# PCB_DYBoard_Bandmaster_V2_SCH3.net
KiCad netlist of a schematic drawn in Altium Designer
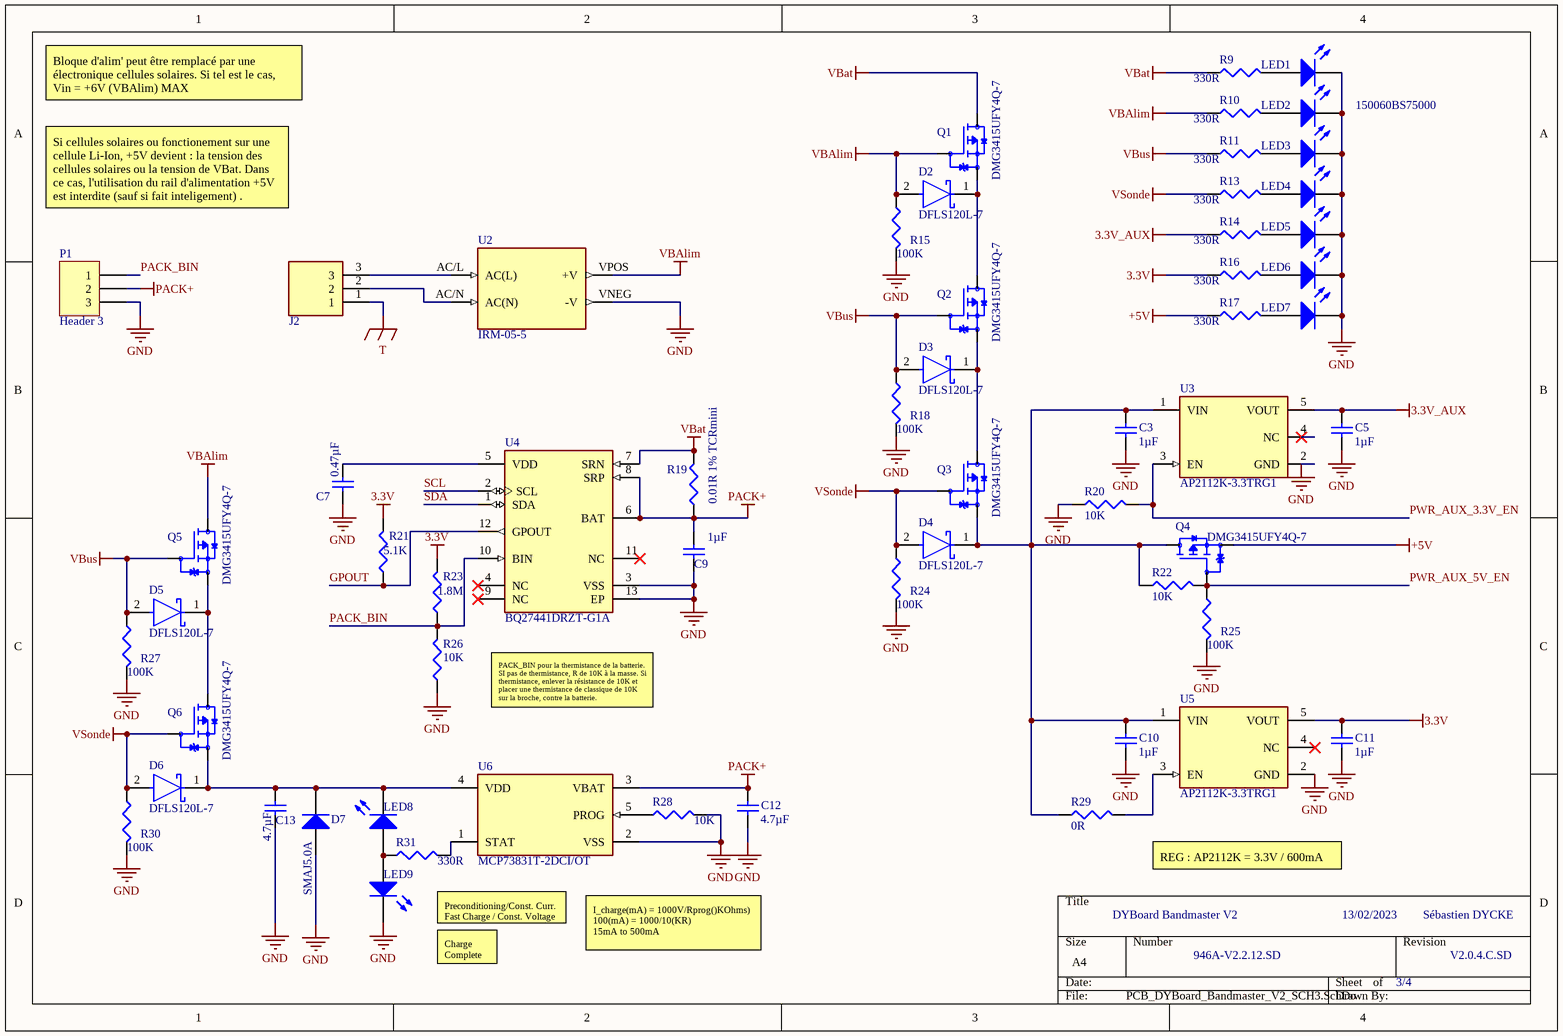
[diagram p0: PCB_DYBoard_Bandmaster_V2_SCH3.SchDoc]

(export (version "E")
  (design (tool "Eeschema 10.0.6"))
  (components
    (comp (ref "C3")
      (value "1µF")
      (footprint "1608[0603]")
      (description "Capacitor (Semiconductor SIM Model)")
      (fields (field (name "Comment") "Cap Semi") (field (name "PUBLISHER") "Altium Limited"))
      (libsource (lib "Miscellaneous Devices") (part "Cap Semi"))
    )
    (comp (ref "C5")
      (value "1µF")
      (footprint "1608[0603]")
      (description "Capacitor (Semiconductor SIM Model)")
      (fields (field (name "Comment") "Cap Semi") (field (name "PUBLISHER") "Altium Limited"))
      (libsource (lib "Miscellaneous Devices") (part "Cap Semi"))
    )
    (comp (ref "C7")
      (value "0.47µF")
      (footprint "1608[0603]")
      (description "Capacitor (Semiconductor SIM Model)")
      (fields (field (name "Comment") "Cap Semi") (field (name "PUBLISHER") "Altium Limited"))
      (libsource (lib "Miscellaneous Devices") (part "Cap Semi"))
    )
    (comp (ref "C9")
      (value "1µF")
      (footprint "1608[0603]")
      (description "Capacitor (Semiconductor SIM Model)")
      (fields (field (name "Comment") "Cap Semi") (field (name "PUBLISHER") "Altium Limited"))
      (libsource (lib "Miscellaneous Devices") (part "Cap Semi"))
    )
    (comp (ref "C10")
      (value "1µF")
      (footprint "1608[0603]")
      (description "Capacitor (Semiconductor SIM Model)")
      (fields (field (name "Comment") "Cap Semi") (field (name "PUBLISHER") "Altium Limited"))
      (libsource (lib "Miscellaneous Devices") (part "Cap Semi"))
    )
    (comp (ref "C11")
      (value "1µF")
      (footprint "1608[0603]")
      (description "Capacitor (Semiconductor SIM Model)")
      (fields (field (name "Comment") "Cap Semi") (field (name "PUBLISHER") "Altium Limited"))
      (libsource (lib "Miscellaneous Devices") (part "Cap Semi"))
    )
    (comp (ref "C12")
      (value "4.7µF")
      (footprint "1608[0603]")
      (description "Capacitor (Semiconductor SIM Model)")
      (fields (field (name "Comment") "Cap Semi") (field (name "PUBLISHER") "Altium Limited"))
      (libsource (lib "Miscellaneous Devices") (part "Cap Semi"))
    )
    (comp (ref "C13")
      (value "4.7µF")
      (footprint "1608[0603]")
      (description "Capacitor (Semiconductor SIM Model)")
      (fields (field (name "Comment") "Cap Semi") (field (name "PUBLISHER") "Altium Limited"))
      (libsource (lib "Miscellaneous Devices") (part "Cap Semi"))
    )
    (comp (ref "D2")
      (value "DFLS120L-7")
      (footprint "FP-PowerDI123-MFG")
      (description "DIODE SCHOTTKY 20V 1A POWERDI123")
      (fields
        (field (name "MANUFACTURER") "Diodes Inc.")
        (field (name "OCTOPART") "https://octopart.com/dfls120l-7-diodes+inc.-328569")
      )
      (libsource (lib "Altium Content Vault") (part "1d6ec82d83fb6aee721767c19dac4b9"))
    )
    (comp (ref "D3")
      (value "DFLS120L-7")
      (footprint "FP-PowerDI123-MFG")
      (description "DIODE SCHOTTKY 20V 1A POWERDI123")
      (fields
        (field (name "MANUFACTURER") "Diodes Inc.")
        (field (name "OCTOPART") "https://octopart.com/dfls120l-7-diodes+inc.-328569")
      )
      (libsource (lib "Altium Content Vault") (part "1d6ec82d83fb6aee721767c19dac4b9"))
    )
    (comp (ref "D4")
      (value "DFLS120L-7")
      (footprint "FP-PowerDI123-MFG")
      (description "DIODE SCHOTTKY 20V 1A POWERDI123")
      (fields
        (field (name "MANUFACTURER") "Diodes Inc.")
        (field (name "OCTOPART") "https://octopart.com/dfls120l-7-diodes+inc.-328569")
      )
      (libsource (lib "Altium Content Vault") (part "1d6ec82d83fb6aee721767c19dac4b9"))
    )
    (comp (ref "D5")
      (value "DFLS120L-7")
      (footprint "FP-PowerDI123-MFG")
      (description "DIODE SCHOTTKY 20V 1A POWERDI123")
      (fields
        (field (name "MANUFACTURER") "Diodes Inc.")
        (field (name "OCTOPART") "https://octopart.com/dfls120l-7-diodes+inc.-328569")
      )
      (libsource (lib "Altium Content Vault") (part "1d6ec82d83fb6aee721767c19dac4b9"))
    )
    (comp (ref "D6")
      (value "DFLS120L-7")
      (footprint "FP-PowerDI123-MFG")
      (description "DIODE SCHOTTKY 20V 1A POWERDI123")
      (fields
        (field (name "MANUFACTURER") "Diodes Inc.")
        (field (name "OCTOPART") "https://octopart.com/dfls120l-7-diodes+inc.-328569")
      )
      (libsource (lib "Altium Content Vault") (part "1d6ec82d83fb6aee721767c19dac4b9"))
    )
    (comp (ref "D7")
      (value "SMAJ5.0A")
      (footprint "BOUR-SMA-2_V")
      (fields (field (name "MANUFACTURER") "Bourns"))
      (libsource (lib "Altium Content Vault") (part "D-AK-2"))
    )
    (comp (ref "J2")
      (value "TBP02R2-381-03BE")
      (footprint "CUI_TBP02R2-381-03BE")
      (description "2~24 Poles, Pluggable, Receptacle, Vertical, 3.81 Pitch, Terminal Block Connector")
      (fields (field (name "MF") "CUI Devices"))
      (libsource (lib "TBP02R2-381-03BE") (part "TBP02R2-381-03BE"))
    )
    (comp (ref "LED1")
      (value "150060BS75000")
      (footprint "0603_A")
      (description "SMD mono-color Chip LED, WL-SMCW, Blue")
      (fields (field (name "MANUFACTURER") "Wuerth Elektronik"))
      (libsource (lib "Altium Content Vault") (part "WE-LED_K1A2-2"))
    )
    (comp (ref "LED2")
      (value "150060BS75000")
      (footprint "0603_A")
      (description "SMD mono-color Chip LED, WL-SMCW, Blue")
      (fields (field (name "MANUFACTURER") "Wuerth Elektronik"))
      (libsource (lib "Altium Content Vault") (part "WE-LED_K1A2-2"))
    )
    (comp (ref "LED3")
      (value "150060BS75000")
      (footprint "0603_A")
      (description "SMD mono-color Chip LED, WL-SMCW, Blue")
      (fields (field (name "MANUFACTURER") "Wuerth Elektronik"))
      (libsource (lib "Altium Content Vault") (part "WE-LED_K1A2-2"))
    )
    (comp (ref "LED4")
      (value "150060BS75000")
      (footprint "0603_A")
      (description "SMD mono-color Chip LED, WL-SMCW, Blue")
      (fields (field (name "MANUFACTURER") "Wuerth Elektronik"))
      (libsource (lib "Altium Content Vault") (part "WE-LED_K1A2-2"))
    )
    (comp (ref "LED5")
      (value "150060BS75000")
      (footprint "0603_A")
      (description "SMD mono-color Chip LED, WL-SMCW, Blue")
      (fields (field (name "MANUFACTURER") "Wuerth Elektronik"))
      (libsource (lib "Altium Content Vault") (part "WE-LED_K1A2-2"))
    )
    (comp (ref "LED6")
      (value "150060BS75000")
      (footprint "0603_A")
      (description "SMD mono-color Chip LED, WL-SMCW, Blue")
      (fields (field (name "MANUFACTURER") "Wuerth Elektronik"))
      (libsource (lib "Altium Content Vault") (part "WE-LED_K1A2-2"))
    )
    (comp (ref "LED7")
      (value "150060BS75000")
      (footprint "0603_A")
      (description "SMD mono-color Chip LED, WL-SMCW, Blue")
      (fields (field (name "MANUFACTURER") "Wuerth Elektronik"))
      (libsource (lib "Altium Content Vault") (part "WE-LED_K1A2-2"))
    )
    (comp (ref "LED8")
      (value "150060BS75000")
      (footprint "0603_A")
      (description "SMD mono-color Chip LED, WL-SMCW, Blue")
      (fields (field (name "MANUFACTURER") "Wuerth Elektronik"))
      (libsource (lib "Altium Content Vault") (part "WE-LED_K1A2-2"))
    )
    (comp (ref "LED9")
      (value "150060BS75000")
      (footprint "0603_A")
      (description "SMD mono-color Chip LED, WL-SMCW, Blue")
      (fields (field (name "MANUFACTURER") "Wuerth Elektronik"))
      (libsource (lib "Altium Content Vault") (part "WE-LED_K1A2-2"))
    )
    (comp (ref "P1")
      (value "Header 3")
      (footprint "HDR1X3")
      (description "Header, 3-Pin")
      (fields (field (name "PUBLISHER") "Altium Limited"))
      (libsource (lib "Miscellaneous Connectors") (part "Header 3"))
    )
    (comp (ref "Q1")
      (value "DMG3415UFY4Q-7")
      (footprint "TRANS_DMG3415UFY4Q-7")
      (description "P-Channel 16V 2.5A _Ta_ 650mW _Ta_ Surface Mount X2-DFN2015-3")
      (fields (field (name "MF") "Diodes Inc.") (field (name "DIGI-KEY_PART_NUMBER") "DMG3415UFY4Q-7DICT-ND"))
      (libsource (lib "DMG3415UFY4Q-7") (part "DMG3415UFY4Q-7"))
    )
    (comp (ref "Q2")
      (value "DMG3415UFY4Q-7")
      (footprint "TRANS_DMG3415UFY4Q-7")
      (description "P-Channel 16V 2.5A _Ta_ 650mW _Ta_ Surface Mount X2-DFN2015-3")
      (fields (field (name "MF") "Diodes Inc.") (field (name "DIGI-KEY_PART_NUMBER") "DMG3415UFY4Q-7DICT-ND"))
      (libsource (lib "DMG3415UFY4Q-7") (part "DMG3415UFY4Q-7"))
    )
    (comp (ref "Q3")
      (value "DMG3415UFY4Q-7")
      (footprint "TRANS_DMG3415UFY4Q-7")
      (description "P-Channel 16V 2.5A _Ta_ 650mW _Ta_ Surface Mount X2-DFN2015-3")
      (fields (field (name "MF") "Diodes Inc.") (field (name "DIGI-KEY_PART_NUMBER") "DMG3415UFY4Q-7DICT-ND"))
      (libsource (lib "DMG3415UFY4Q-7") (part "DMG3415UFY4Q-7"))
    )
    (comp (ref "Q4")
      (value "DMG3415UFY4Q-7")
      (footprint "TRANS_DMG3415UFY4Q-7")
      (description "P-Channel 16V 2.5A _Ta_ 650mW _Ta_ Surface Mount X2-DFN2015-3")
      (fields (field (name "MF") "Diodes Inc.") (field (name "DIGI-KEY_PART_NUMBER") "DMG3415UFY4Q-7DICT-ND"))
      (libsource (lib "DMG3415UFY4Q-7") (part "DMG3415UFY4Q-7"))
    )
    (comp (ref "Q5")
      (value "DMG3415UFY4Q-7")
      (footprint "TRANS_DMG3415UFY4Q-7")
      (description "P-Channel 16V 2.5A _Ta_ 650mW _Ta_ Surface Mount X2-DFN2015-3")
      (fields (field (name "MF") "Diodes Inc.") (field (name "DIGI-KEY_PART_NUMBER") "DMG3415UFY4Q-7DICT-ND"))
      (libsource (lib "DMG3415UFY4Q-7") (part "DMG3415UFY4Q-7"))
    )
    (comp (ref "Q6")
      (value "DMG3415UFY4Q-7")
      (footprint "TRANS_DMG3415UFY4Q-7")
      (description "P-Channel 16V 2.5A _Ta_ 650mW _Ta_ Surface Mount X2-DFN2015-3")
      (fields (field (name "MF") "Diodes Inc.") (field (name "DIGI-KEY_PART_NUMBER") "DMG3415UFY4Q-7DICT-ND"))
      (libsource (lib "DMG3415UFY4Q-7") (part "DMG3415UFY4Q-7"))
    )
    (comp (ref "R9")
      (value "330R")
      (footprint "J1-0603")
      (description "Resistor")
      (fields (field (name "Comment") "Res3") (field (name "PUBLISHER") "Altium Limited"))
      (libsource (lib "Miscellaneous Devices") (part "Res3"))
    )
    (comp (ref "R10")
      (value "330R")
      (footprint "J1-0603")
      (description "Resistor")
      (fields (field (name "Comment") "Res3") (field (name "PUBLISHER") "Altium Limited"))
      (libsource (lib "Miscellaneous Devices") (part "Res3"))
    )
    (comp (ref "R11")
      (value "330R")
      (footprint "J1-0603")
      (description "Resistor")
      (fields (field (name "Comment") "Res3") (field (name "PUBLISHER") "Altium Limited"))
      (libsource (lib "Miscellaneous Devices") (part "Res3"))
    )
    (comp (ref "R13")
      (value "330R")
      (footprint "J1-0603")
      (description "Resistor")
      (fields (field (name "Comment") "Res3") (field (name "PUBLISHER") "Altium Limited"))
      (libsource (lib "Miscellaneous Devices") (part "Res3"))
    )
    (comp (ref "R14")
      (value "330R")
      (footprint "J1-0603")
      (description "Resistor")
      (fields (field (name "Comment") "Res3") (field (name "PUBLISHER") "Altium Limited"))
      (libsource (lib "Miscellaneous Devices") (part "Res3"))
    )
    (comp (ref "R15")
      (value "100K")
      (footprint "J1-0603")
      (description "Resistor")
      (fields (field (name "Comment") "Res3") (field (name "PUBLISHER") "Altium Limited"))
      (libsource (lib "Miscellaneous Devices") (part "Res3"))
    )
    (comp (ref "R16")
      (value "330R")
      (footprint "J1-0603")
      (description "Resistor")
      (fields (field (name "Comment") "Res3") (field (name "PUBLISHER") "Altium Limited"))
      (libsource (lib "Miscellaneous Devices") (part "Res3"))
    )
    (comp (ref "R17")
      (value "330R")
      (footprint "J1-0603")
      (description "Resistor")
      (fields (field (name "Comment") "Res3") (field (name "PUBLISHER") "Altium Limited"))
      (libsource (lib "Miscellaneous Devices") (part "Res3"))
    )
    (comp (ref "R18")
      (value "100K")
      (footprint "J1-0603")
      (description "Resistor")
      (fields (field (name "Comment") "Res3") (field (name "PUBLISHER") "Altium Limited"))
      (libsource (lib "Miscellaneous Devices") (part "Res3"))
    )
    (comp (ref "R19")
      (value "0.01R 1% TCRmini")
      (footprint "J1-0603")
      (description "Resistor")
      (fields (field (name "Comment") "Res3") (field (name "PUBLISHER") "Altium Limited"))
      (libsource (lib "Miscellaneous Devices") (part "Res3"))
    )
    (comp (ref "R20")
      (value "10K")
      (footprint "J1-0603")
      (description "Resistor")
      (fields (field (name "Comment") "Res3") (field (name "PUBLISHER") "Altium Limited"))
      (libsource (lib "Miscellaneous Devices") (part "Res3"))
    )
    (comp (ref "R21")
      (value "5.1K")
      (footprint "J1-0603")
      (description "Resistor")
      (fields (field (name "Comment") "Res3") (field (name "PUBLISHER") "Altium Limited"))
      (libsource (lib "Miscellaneous Devices") (part "Res3"))
    )
    (comp (ref "R22")
      (value "10K")
      (footprint "J1-0603")
      (description "Resistor")
      (fields (field (name "Comment") "Res3") (field (name "PUBLISHER") "Altium Limited"))
      (libsource (lib "Miscellaneous Devices") (part "Res3"))
    )
    (comp (ref "R23")
      (value "1.8M")
      (footprint "J1-0603")
      (description "Resistor")
      (fields (field (name "Comment") "Res3") (field (name "PUBLISHER") "Altium Limited"))
      (libsource (lib "Miscellaneous Devices") (part "Res3"))
    )
    (comp (ref "R24")
      (value "100K")
      (footprint "J1-0603")
      (description "Resistor")
      (fields (field (name "Comment") "Res3") (field (name "PUBLISHER") "Altium Limited"))
      (libsource (lib "Miscellaneous Devices") (part "Res3"))
    )
    (comp (ref "R25")
      (value "100K")
      (footprint "J1-0603")
      (description "Resistor")
      (fields (field (name "Comment") "Res3") (field (name "PUBLISHER") "Altium Limited"))
      (libsource (lib "Miscellaneous Devices") (part "Res3"))
    )
    (comp (ref "R26")
      (value "10K")
      (footprint "J1-0603")
      (description "Resistor")
      (fields (field (name "Comment") "Res3") (field (name "PUBLISHER") "Altium Limited"))
      (libsource (lib "Miscellaneous Devices") (part "Res3"))
    )
    (comp (ref "R27")
      (value "100K")
      (footprint "J1-0603")
      (description "Resistor")
      (fields (field (name "Comment") "Res3") (field (name "PUBLISHER") "Altium Limited"))
      (libsource (lib "Miscellaneous Devices") (part "Res3"))
    )
    (comp (ref "R28")
      (value "10K")
      (footprint "J1-0603")
      (description "Resistor")
      (fields (field (name "Comment") "Res3") (field (name "PUBLISHER") "Altium Limited"))
      (libsource (lib "Miscellaneous Devices") (part "Res3"))
    )
    (comp (ref "R29")
      (value "0R")
      (footprint "J1-0603")
      (description "Resistor")
      (fields (field (name "Comment") "Res3") (field (name "PUBLISHER") "Altium Limited"))
      (libsource (lib "Miscellaneous Devices") (part "Res3"))
    )
    (comp (ref "R30")
      (value "100K")
      (footprint "J1-0603")
      (description "Resistor")
      (fields (field (name "Comment") "Res3") (field (name "PUBLISHER") "Altium Limited"))
      (libsource (lib "Miscellaneous Devices") (part "Res3"))
    )
    (comp (ref "R31")
      (value "330R")
      (footprint "J1-0603")
      (description "Resistor")
      (fields (field (name "Comment") "Res3") (field (name "PUBLISHER") "Altium Limited"))
      (libsource (lib "Miscellaneous Devices") (part "Res3"))
    )
    (comp (ref "U2")
      (value "IRM-05-5")
      (footprint "CONV_IRM-05-5")
      (description "Enclosed AC DC Converters 1 Uitgang 5V 1A 85 ~ 305 VAC, 120 ~ 430 VDC Input")
      (fields (field (name "MF") "MEAN WELL"))
      (libsource (lib "IRM-05-5") (part "IRM-05-5"))
    )
    (comp (ref "U3")
      (value "AP2112K-3.3TRG1")
      (footprint "FP-SOT25-IPC_A")
      (description "IC REG LINEAR 3.3V 600MA SOT25")
      (libsource (lib "Altium Content Vault") (part "c8ab751aee5229183125ab046a11caa"))
    )
    (comp (ref "U4")
      (value "BQ27441DRZT-G1A")
      (footprint "FP-DRZ0012A-MFG")
      (description "IC BATT FUEL GAUGE LICOO2 12SON")
      (fields
        (field (name "OCTOPART") "https://octopart.com/bq27441drzt-g1a-texas+instruments-30555831")
        (field (name "MANUFACTURER") "Texas Instruments")
      )
      (libsource (lib "Altium Content Vault") (part "c803e035ce0891ae19034f27297cdee"))
    )
    (comp (ref "U5")
      (value "AP2112K-3.3TRG1")
      (footprint "FP-SOT25-IPC_A")
      (description "IC REG LINEAR 3.3V 600MA SOT25")
      (libsource (lib "Altium Content Vault") (part "c8ab751aee5229183125ab046a11caa"))
    )
    (comp (ref "U6")
      (value "MCP73831T-2DCI/OT")
      (footprint "FP-C04-091-OT-IPC_B")
      (description "IC CONTROLLR LI-ION 4.2V SOT23-5")
      (libsource (lib "Altium Content Vault") (part "61f5a3bb3429d9e0caadea342aa3b19"))
    )
  )
  (nets
    (net (code "1") (name "+5V") (class "Default")
      (node (ref "Q4") (pin "2") (pinfunction "S_2") (pintype "passive"))
      (node (ref "R17") (pin "1") (pinfunction "1_1") (pintype "passive"))
    )
    (net (code "2") (name "/GPOUT") (class "Default")
      (node (ref "R21") (pin "1") (pinfunction "1_1") (pintype "passive"))
      (node (ref "U4") (pin "12") (pinfunction "GPOUT_12") (pintype "output"))
    )
    (net (code "3") (name "/PACK_BIN") (class "Default")
      (node (ref "P1") (pin "1") (pinfunction "1_1") (pintype "passive"))
      (node (ref "R23") (pin "1") (pinfunction "1_1") (pintype "passive"))
      (node (ref "R26") (pin "2") (pinfunction "2_2") (pintype "passive"))
      (node (ref "U4") (pin "10") (pinfunction "BIN_10") (pintype "input"))
    )
    (net (code "4") (name "/PWR_AUX_3.3V_EN") (class "Default")
      (node (ref "R20") (pin "2") (pinfunction "2_2") (pintype "passive"))
      (node (ref "U3") (pin "3") (pinfunction "EN_3") (pintype "input"))
    )
    (net (code "5") (name "/PWR_AUX_5V_EN") (class "Default")
      (node (ref "Q4") (pin "1") (pinfunction "G_1") (pintype "passive"))
      (node (ref "R22") (pin "2") (pinfunction "2_2") (pintype "passive"))
      (node (ref "R25") (pin "1") (pinfunction "1_1") (pintype "passive"))
    )
    (net (code "6") (name "/SCL") (class "Default")
      (node (ref "U4") (pin "2") (pinfunction "SCL_2") (pintype "bidirectional"))
    )
    (net (code "7") (name "/SDA") (class "Default")
      (node (ref "U4") (pin "1") (pinfunction "SDA_1") (pintype "bidirectional"))
    )
    (net (code "8") (name "3.3V") (class "Default")
      (node (ref "C11") (pin "2") (pinfunction "2_2") (pintype "passive"))
      (node (ref "R16") (pin "1") (pinfunction "1_1") (pintype "passive"))
      (node (ref "R21") (pin "2") (pinfunction "2_2") (pintype "passive"))
      (node (ref "R23") (pin "2") (pinfunction "2_2") (pintype "passive"))
      (node (ref "U5") (pin "5") (pinfunction "VOUT_5") (pintype "power_in"))
    )
    (net (code "9") (name "3.3V_AUX") (class "Default")
      (node (ref "C5") (pin "2") (pinfunction "2_2") (pintype "passive"))
      (node (ref "R14") (pin "1") (pinfunction "1_1") (pintype "passive"))
      (node (ref "U3") (pin "5") (pinfunction "VOUT_5") (pintype "power_in"))
    )
    (net (code "10") (name "GND") (class "Default")
      (node (ref "C10") (pin "1") (pinfunction "1_1") (pintype "passive"))
      (node (ref "C11") (pin "1") (pinfunction "1_1") (pintype "passive"))
      (node (ref "C12") (pin "1") (pinfunction "1_1") (pintype "passive"))
      (node (ref "C13") (pin "1") (pinfunction "1_1") (pintype "passive"))
      (node (ref "C3") (pin "1") (pinfunction "1_1") (pintype "passive"))
      (node (ref "C5") (pin "1") (pinfunction "1_1") (pintype "passive"))
      (node (ref "C7") (pin "1") (pinfunction "1_1") (pintype "passive"))
      (node (ref "C9") (pin "1") (pinfunction "1_1") (pintype "passive"))
      (node (ref "D7") (pin "1") (pinfunction "A_1") (pintype "passive"))
      (node (ref "LED1") (pin "1") (pinfunction "K_1") (pintype "passive"))
      (node (ref "LED2") (pin "1") (pinfunction "K_1") (pintype "passive"))
      (node (ref "LED3") (pin "1") (pinfunction "K_1") (pintype "passive"))
      (node (ref "LED4") (pin "1") (pinfunction "K_1") (pintype "passive"))
      (node (ref "LED5") (pin "1") (pinfunction "K_1") (pintype "passive"))
      (node (ref "LED6") (pin "1") (pinfunction "K_1") (pintype "passive"))
      (node (ref "LED7") (pin "1") (pinfunction "K_1") (pintype "passive"))
      (node (ref "LED9") (pin "1") (pinfunction "K_1") (pintype "passive"))
      (node (ref "P1") (pin "3") (pinfunction "3_3") (pintype "passive"))
      (node (ref "R15") (pin "2") (pinfunction "2_2") (pintype "passive"))
      (node (ref "R18") (pin "2") (pinfunction "2_2") (pintype "passive"))
      (node (ref "R20") (pin "1") (pinfunction "1_1") (pintype "passive"))
      (node (ref "R24") (pin "2") (pinfunction "2_2") (pintype "passive"))
      (node (ref "R25") (pin "2") (pinfunction "2_2") (pintype "passive"))
      (node (ref "R26") (pin "1") (pinfunction "1_1") (pintype "passive"))
      (node (ref "R27") (pin "2") (pinfunction "2_2") (pintype "passive"))
      (node (ref "R28") (pin "2") (pinfunction "2_2") (pintype "passive"))
      (node (ref "R30") (pin "2") (pinfunction "2_2") (pintype "passive"))
      (node (ref "U2") (pin "VNEG") (pinfunction "-V_VNEG") (pintype "output"))
      (node (ref "U3") (pin "2") (pinfunction "GND_2") (pintype "power_in"))
      (node (ref "U4") (pin "13") (pinfunction "EP_13") (pintype "power_in"))
      (node (ref "U4") (pin "3") (pinfunction "VSS_3") (pintype "power_in"))
      (node (ref "U5") (pin "2") (pinfunction "GND_2") (pintype "power_in"))
      (node (ref "U6") (pin "2") (pinfunction "VSS_2") (pintype "power_in"))
    )
    (net (code "11") (name "Net-(D2-C)") (class "Default")
      (node (ref "D2") (pin "1") (pinfunction "C_1") (pintype "passive"))
      (node (ref "Q1") (pin "2") (pinfunction "S_2") (pintype "passive"))
      (node (ref "Q2") (pin "3") (pinfunction "D_3") (pintype "passive"))
    )
    (net (code "12") (name "Net-(D3-C)") (class "Default")
      (node (ref "D3") (pin "1") (pinfunction "C_1") (pintype "passive"))
      (node (ref "Q2") (pin "2") (pinfunction "S_2") (pintype "passive"))
      (node (ref "Q3") (pin "3") (pinfunction "D_3") (pintype "passive"))
    )
    (net (code "13") (name "Net-(D4-C)") (class "Default")
      (node (ref "C10") (pin "2") (pinfunction "2_2") (pintype "passive"))
      (node (ref "C3") (pin "2") (pinfunction "2_2") (pintype "passive"))
      (node (ref "D4") (pin "1") (pinfunction "C_1") (pintype "passive"))
      (node (ref "Q3") (pin "2") (pinfunction "S_2") (pintype "passive"))
      (node (ref "Q4") (pin "3") (pinfunction "D_3") (pintype "passive"))
      (node (ref "R22") (pin "1") (pinfunction "1_1") (pintype "passive"))
      (node (ref "R29") (pin "1") (pinfunction "1_1") (pintype "passive"))
      (node (ref "U3") (pin "1") (pinfunction "VIN_1") (pintype "power_in"))
      (node (ref "U5") (pin "1") (pinfunction "VIN_1") (pintype "power_in"))
    )
    (net (code "14") (name "Net-(D5-C)") (class "Default")
      (node (ref "D5") (pin "1") (pinfunction "C_1") (pintype "passive"))
      (node (ref "Q5") (pin "2") (pinfunction "S_2") (pintype "passive"))
      (node (ref "Q6") (pin "3") (pinfunction "D_3") (pintype "passive"))
    )
    (net (code "15") (name "Net-(D6-C)") (class "Default")
      (node (ref "C13") (pin "2") (pinfunction "2_2") (pintype "passive"))
      (node (ref "D6") (pin "1") (pinfunction "C_1") (pintype "passive"))
      (node (ref "D7") (pin "2") (pinfunction "K_2") (pintype "passive"))
      (node (ref "LED8") (pin "1") (pinfunction "K_1") (pintype "passive"))
      (node (ref "Q6") (pin "2") (pinfunction "S_2") (pintype "passive"))
      (node (ref "U6") (pin "4") (pinfunction "VDD_4") (pintype "open_emitter"))
    )
    (net (code "16") (name "Net-(LED1-A)") (class "Default")
      (node (ref "LED1") (pin "2") (pinfunction "A_2") (pintype "passive"))
      (node (ref "R9") (pin "2") (pinfunction "2_2") (pintype "passive"))
    )
    (net (code "17") (name "Net-(LED2-A)") (class "Default")
      (node (ref "LED2") (pin "2") (pinfunction "A_2") (pintype "passive"))
      (node (ref "R10") (pin "2") (pinfunction "2_2") (pintype "passive"))
    )
    (net (code "18") (name "Net-(LED3-A)") (class "Default")
      (node (ref "LED3") (pin "2") (pinfunction "A_2") (pintype "passive"))
      (node (ref "R11") (pin "2") (pinfunction "2_2") (pintype "passive"))
    )
    (net (code "19") (name "Net-(LED4-A)") (class "Default")
      (node (ref "LED4") (pin "2") (pinfunction "A_2") (pintype "passive"))
      (node (ref "R13") (pin "2") (pinfunction "2_2") (pintype "passive"))
    )
    (net (code "20") (name "Net-(LED5-A)") (class "Default")
      (node (ref "LED5") (pin "2") (pinfunction "A_2") (pintype "passive"))
      (node (ref "R14") (pin "2") (pinfunction "2_2") (pintype "passive"))
    )
    (net (code "21") (name "Net-(LED6-A)") (class "Default")
      (node (ref "LED6") (pin "2") (pinfunction "A_2") (pintype "passive"))
      (node (ref "R16") (pin "2") (pinfunction "2_2") (pintype "passive"))
    )
    (net (code "22") (name "Net-(LED7-A)") (class "Default")
      (node (ref "LED7") (pin "2") (pinfunction "A_2") (pintype "passive"))
      (node (ref "R17") (pin "2") (pinfunction "2_2") (pintype "passive"))
    )
    (net (code "23") (name "Net-(LED8-A)") (class "Default")
      (node (ref "LED8") (pin "2") (pinfunction "A_2") (pintype "passive"))
      (node (ref "LED9") (pin "2") (pinfunction "A_2") (pintype "passive"))
      (node (ref "R31") (pin "1") (pinfunction "1_1") (pintype "passive"))
    )
    (net (code "24") (name "Net-(U2-AC(L))") (class "Default")
      (node (ref "J2") (pin "3") (pinfunction "3_3") (pintype "passive"))
      (node (ref "U2") (pin "AC/L") (pinfunction "AC(L)_AC/L") (pintype "input"))
    )
    (net (code "25") (name "Net-(U2-AC(N))") (class "Default")
      (node (ref "J2") (pin "2") (pinfunction "2_2") (pintype "passive"))
      (node (ref "U2") (pin "AC/N") (pinfunction "AC(N)_AC/N") (pintype "input"))
    )
    (net (code "26") (name "Net-(U4-VDD)") (class "Default")
      (node (ref "C7") (pin "2") (pinfunction "2_2") (pintype "passive"))
      (node (ref "U4") (pin "5") (pinfunction "VDD_5") (pintype "power_in"))
    )
    (net (code "27") (name "Net-(U5-EN)") (class "Default")
      (node (ref "R29") (pin "2") (pinfunction "2_2") (pintype "passive"))
      (node (ref "U5") (pin "3") (pinfunction "EN_3") (pintype "input"))
    )
    (net (code "28") (name "Net-(U6-PROG)") (class "Default")
      (node (ref "R28") (pin "1") (pinfunction "1_1") (pintype "passive"))
      (node (ref "U6") (pin "5") (pinfunction "PROG_5") (pintype "input"))
    )
    (net (code "29") (name "Net-(U6-STAT)") (class "Default")
      (node (ref "R31") (pin "2") (pinfunction "2_2") (pintype "passive"))
      (node (ref "U6") (pin "1") (pinfunction "STAT_1") (pintype "passive"))
    )
    (net (code "30") (name "PACK+") (class "Default")
      (node (ref "C12") (pin "2") (pinfunction "2_2") (pintype "passive"))
      (node (ref "C9") (pin "2") (pinfunction "2_2") (pintype "passive"))
      (node (ref "P1") (pin "2") (pinfunction "2_2") (pintype "passive"))
      (node (ref "R19") (pin "1") (pinfunction "1_1") (pintype "passive"))
      (node (ref "U4") (pin "6") (pinfunction "BAT_6") (pintype "power_in"))
      (node (ref "U4") (pin "8") (pinfunction "SRP_8") (pintype "input"))
      (node (ref "U6") (pin "3") (pinfunction "VBAT_3") (pintype "power_in"))
    )
    (net (code "31") (name "T") (class "Default")
      (node (ref "J2") (pin "1") (pinfunction "1_1") (pintype "passive"))
    )
    (net (code "32") (name "VBAlim") (class "Default")
      (node (ref "D2") (pin "2") (pinfunction "A_2") (pintype "passive"))
      (node (ref "Q1") (pin "1") (pinfunction "G_1") (pintype "passive"))
      (node (ref "Q5") (pin "3") (pinfunction "D_3") (pintype "passive"))
      (node (ref "R10") (pin "1") (pinfunction "1_1") (pintype "passive"))
      (node (ref "R15") (pin "1") (pinfunction "1_1") (pintype "passive"))
      (node (ref "U2") (pin "VPOS") (pinfunction "+V_VPOS") (pintype "output"))
    )
    (net (code "33") (name "VBat") (class "Default")
      (node (ref "Q1") (pin "3") (pinfunction "D_3") (pintype "passive"))
      (node (ref "R19") (pin "2") (pinfunction "2_2") (pintype "passive"))
      (node (ref "R9") (pin "1") (pinfunction "1_1") (pintype "passive"))
      (node (ref "U4") (pin "7") (pinfunction "SRN_7") (pintype "input"))
    )
    (net (code "34") (name "VBus") (class "Default")
      (node (ref "D3") (pin "2") (pinfunction "A_2") (pintype "passive"))
      (node (ref "D5") (pin "2") (pinfunction "A_2") (pintype "passive"))
      (node (ref "Q2") (pin "1") (pinfunction "G_1") (pintype "passive"))
      (node (ref "Q5") (pin "1") (pinfunction "G_1") (pintype "passive"))
      (node (ref "R11") (pin "1") (pinfunction "1_1") (pintype "passive"))
      (node (ref "R18") (pin "1") (pinfunction "1_1") (pintype "passive"))
      (node (ref "R27") (pin "1") (pinfunction "1_1") (pintype "passive"))
    )
    (net (code "35") (name "VSonde") (class "Default")
      (node (ref "D4") (pin "2") (pinfunction "A_2") (pintype "passive"))
      (node (ref "D6") (pin "2") (pinfunction "A_2") (pintype "passive"))
      (node (ref "Q3") (pin "1") (pinfunction "G_1") (pintype "passive"))
      (node (ref "Q6") (pin "1") (pinfunction "G_1") (pintype "passive"))
      (node (ref "R13") (pin "1") (pinfunction "1_1") (pintype "passive"))
      (node (ref "R24") (pin "1") (pinfunction "1_1") (pintype "passive"))
      (node (ref "R30") (pin "1") (pinfunction "1_1") (pintype "passive"))
    )
    (net (code "36") (name "unconnected-(U3-NC-Pad4)") (class "Default")
      (node (ref "U3") (pin "4") (pinfunction "NC_4") (pintype "passive+no_connect"))
    )
    (net (code "37") (name "unconnected-(U4-NC-Pad4)") (class "Default")
      (node (ref "U4") (pin "4") (pinfunction "NC_4") (pintype "passive+no_connect"))
    )
    (net (code "38") (name "unconnected-(U4-NC-Pad9)") (class "Default")
      (node (ref "U4") (pin "9") (pinfunction "NC_9") (pintype "power_in+no_connect"))
    )
    (net (code "39") (name "unconnected-(U4-NC-Pad11)") (class "Default")
      (node (ref "U4") (pin "11") (pinfunction "NC_11") (pintype "passive+no_connect"))
    )
    (net (code "40") (name "unconnected-(U5-NC-Pad4)") (class "Default")
      (node (ref "U5") (pin "4") (pinfunction "NC_4") (pintype "passive+no_connect"))
    )
  )
)
